# ownduino-tiny-cdc.net
KiCad netlist of a schematic drawn in EAGLE
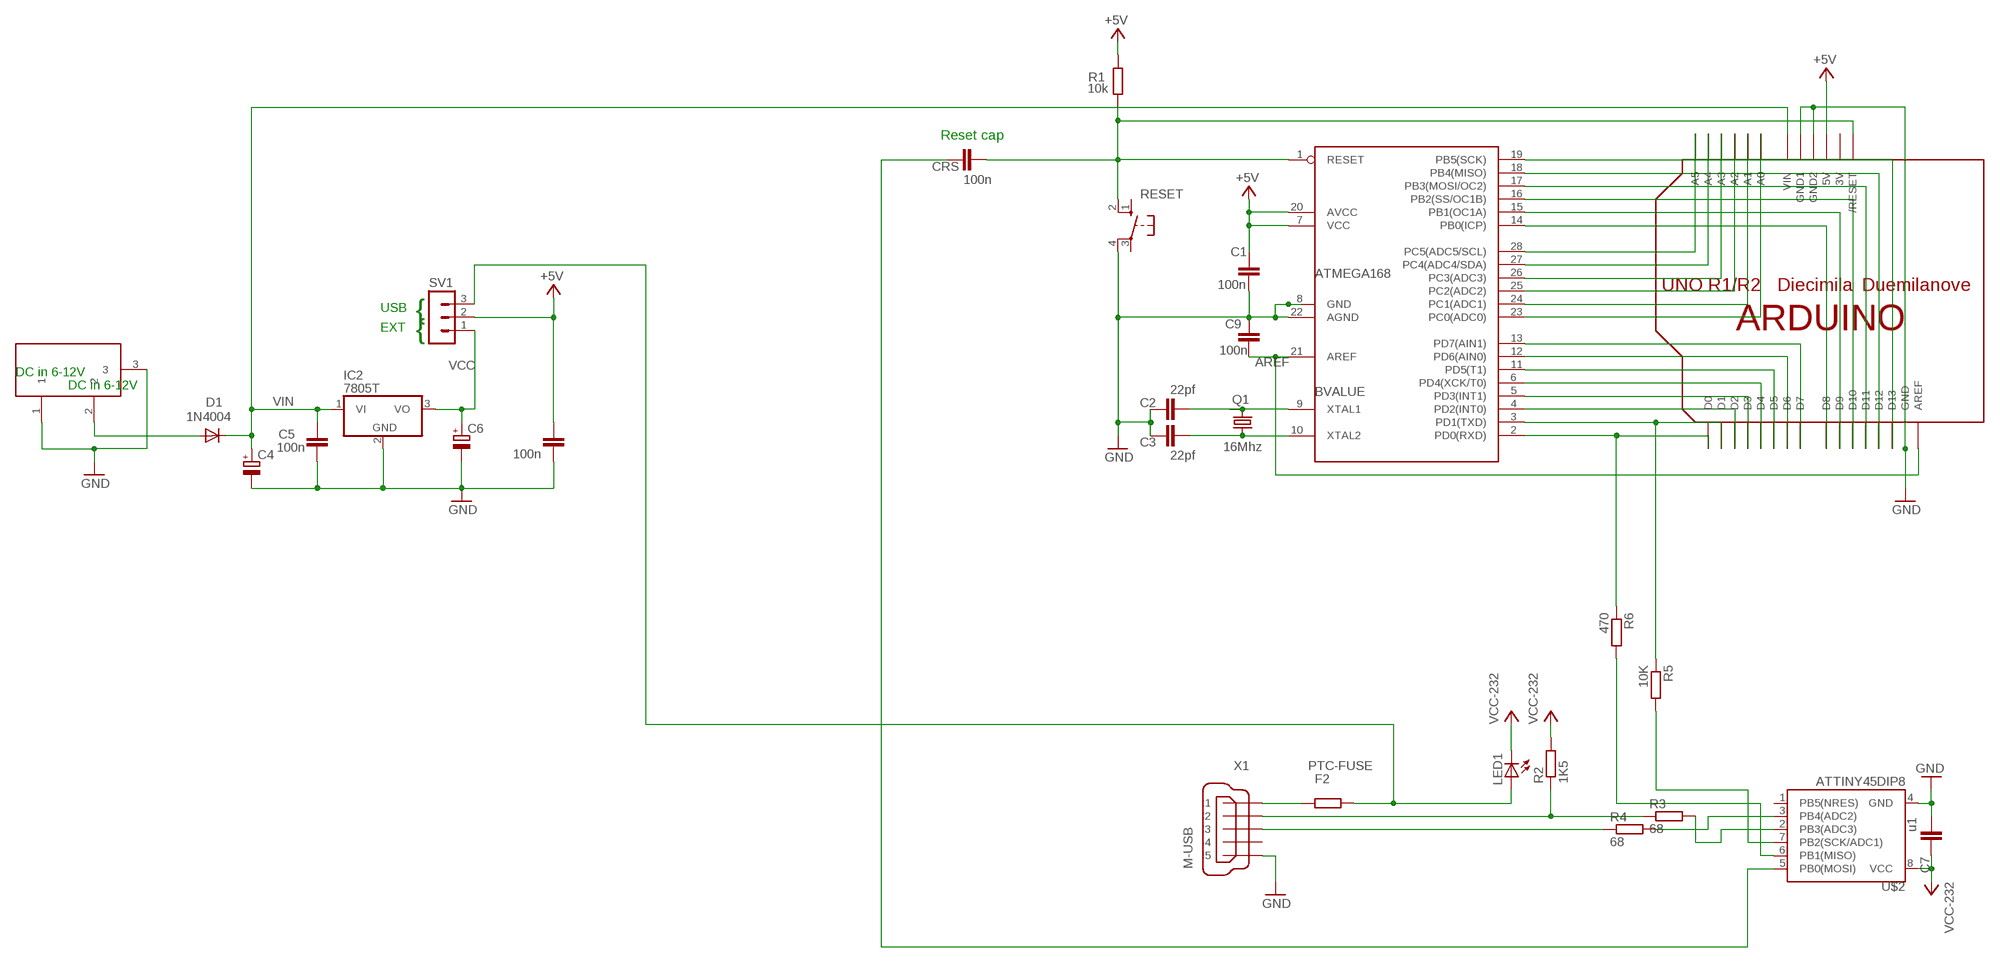
[diagram p0: schematic, sheet 1]

(export (version "E")
  (design (tool "Eeschema 10.0.6"))
  (components
    (comp (ref "BVALUE")
      (value "ATMEGA168")
      (footprint "eagle-import:DIL28-3")
      (libsource (lib "eagle-import") (part "MEGA8-P"))
    )
    (comp (ref "C1")
      (value "100n")
      (footprint "eagle-import:C025-024X044")
      (libsource (lib "eagle-import") (part "C-EU025-024X044"))
    )
    (comp (ref "C2")
      (value "22pf")
      (footprint "eagle-import:C025-024X044")
      (libsource (lib "eagle-import") (part "C-EU025-024X044"))
    )
    (comp (ref "C3")
      (value "22pf")
      (footprint "eagle-import:C025-024X044")
      (libsource (lib "eagle-import") (part "C-EU025-024X044"))
    )
    (comp (ref "C4")
      (value "CPOL-EUE2.5-6")
      (footprint "eagle-import:E2,5-6")
      (libsource (lib "eagle-import") (part "CPOL-EUE2.5-6"))
    )
    (comp (ref "C5")
      (value "100n")
      (footprint "eagle-import:C025-024X044")
      (libsource (lib "eagle-import") (part "C-EU025-024X044"))
    )
    (comp (ref "C6")
      (value "CPOL-EUE2.5-6")
      (footprint "eagle-import:E2,5-6")
      (libsource (lib "eagle-import") (part "CPOL-EUE2.5-6"))
    )
    (comp (ref "C7")
      (value "u1")
      (footprint "eagle-import:C025-024X044")
      (libsource (lib "eagle-import") (part "C-EU025-024X044"))
    )
    (comp (ref "C9")
      (value "100n")
      (footprint "eagle-import:C025-024X044")
      (libsource (lib "eagle-import") (part "C-EU025-024X044"))
    )
    (comp (ref "C10")
      (value "100n")
      (footprint "eagle-import:C025-024X044")
      (libsource (lib "eagle-import") (part "C-EU025-024X044"))
    )
    (comp (ref "CRS")
      (value "100n")
      (footprint "eagle-import:C025-024X044")
      (libsource (lib "eagle-import") (part "C-EU025-024X044"))
    )
    (comp (ref "D1")
      (value "1N4004")
      (footprint "eagle-import:DIODE-0.4")
      (libsource (lib "eagle-import") (part "DIODEPTH"))
    )
    (comp (ref "DC1")
      (value "9V in")
      (footprint "eagle-import:DC-21MM")
      (libsource (lib "eagle-import") (part "DC21MMX"))
    )
    (comp (ref "F2")
      (value "PTC-FUSE")
      (footprint "eagle-import:0204_5")
      (libsource (lib "eagle-import") (part "R-EU_0204/5"))
    )
    (comp (ref "IC2")
      (value "7805T")
      (footprint "eagle-import:TO220H")
      (libsource (lib "eagle-import") (part "78T05"))
    )
    (comp (ref "LED1")
      (value "LED3MM")
      (footprint "eagle-import:LED3MM")
      (libsource (lib "eagle-import") (part "LED3MM"))
    )
    (comp (ref "Q1")
      (value "16Mhz")
      (footprint "eagle-import:HC49U-V")
      (libsource (lib "eagle-import") (part "CRYSTALHC49U-V"))
    )
    (comp (ref "R1")
      (value "10k")
      (footprint "eagle-import:0204_7")
      (libsource (lib "eagle-import") (part "R-EU_0204/7"))
    )
    (comp (ref "R2")
      (value "1K5")
      (footprint "eagle-import:0204V")
      (libsource (lib "eagle-import") (part "R-EU_0204/2V"))
    )
    (comp (ref "R3")
      (value "68")
      (footprint "eagle-import:0204V")
      (libsource (lib "eagle-import") (part "R-EU_0204/2V"))
    )
    (comp (ref "R4")
      (value "68")
      (footprint "eagle-import:0204_5")
      (libsource (lib "eagle-import") (part "R-EU_0204/5"))
    )
    (comp (ref "R5")
      (value "10K")
      (footprint "eagle-import:0204_7")
      (libsource (lib "eagle-import") (part "R-EU_0204/7"))
    )
    (comp (ref "R6")
      (value "470")
      (footprint "eagle-import:0204_7")
      (libsource (lib "eagle-import") (part "R-EU_0204/7"))
    )
    (comp (ref "RESET")
      (value "10-XX")
      (footprint "eagle-import:B3F-10XX")
      (libsource (lib "eagle-import") (part "10-XX"))
    )
    (comp (ref "SV1")
      (value "MA03-1")
      (footprint "eagle-import:MA03-1")
      (libsource (lib "eagle-import") (part "MA03-1"))
    )
    (comp (ref "U$1")
      (value "ARDUINOUNO")
      (footprint "eagle-import:ARDUINO")
      (libsource (lib "eagle-import") (part "ARDUINOUNO"))
    )
    (comp (ref "U$2")
      (value "ATTINY45DIP8")
      (footprint "eagle-import:DIP08")
      (libsource (lib "eagle-import") (part "ATTINY45DIP8"))
    )
    (comp (ref "X1")
      (value "M-USB")
      (footprint "eagle-import:32005-601")
      (libsource (lib "eagle-import") (part "MINI-USB_SHIELD5P2-32005-601"))
    )
  )
  (nets
    (net (code "1") (name "+5V") (class "Default")
      (node (ref "BVALUE") (pin "20") (pinfunction "AVCC_20") (pintype "bidirectional"))
      (node (ref "BVALUE") (pin "7") (pinfunction "VCC_7") (pintype "bidirectional"))
      (node (ref "C1") (pin "1") (pinfunction "1_1") (pintype "passive"))
      (node (ref "C10") (pin "2") (pinfunction "2_2") (pintype "passive"))
      (node (ref "R1") (pin "2") (pinfunction "2_2") (pintype "passive"))
      (node (ref "SV1") (pin "2") (pinfunction "2_2") (pintype "passive"))
      (node (ref "U$1") (pin "5V") (pinfunction "5V_5V") (pintype "power_in"))
    )
    (net (code "2") (name "/3V") (class "Default")
      (node (ref "U$1") (pin "3V") (pinfunction "3V_3V") (pintype "power_in"))
    )
    (net (code "3") (name "/AREF") (class "Default")
      (node (ref "BVALUE") (pin "21") (pinfunction "AREF_21") (pintype "bidirectional"))
      (node (ref "C9") (pin "1") (pinfunction "1_1") (pintype "passive"))
      (node (ref "U$1") (pin "AREF") (pinfunction "AREF_AREF") (pintype "bidirectional"))
    )
    (net (code "4") (name "/VIN") (class "Default")
      (node (ref "C4") (pin "+") (pinfunction "+_+") (pintype "passive"))
      (node (ref "C5") (pin "2") (pinfunction "2_2") (pintype "passive"))
      (node (ref "D1") (pin "C") (pinfunction "C_C") (pintype "passive"))
      (node (ref "IC2") (pin "1") (pinfunction "VI_1") (pintype "input"))
      (node (ref "U$1") (pin "VIN") (pinfunction "VIN_VIN") (pintype "power_in"))
    )
    (net (code "5") (name "GND") (class "Default")
      (node (ref "BVALUE") (pin "22") (pinfunction "AGND_22") (pintype "bidirectional"))
      (node (ref "BVALUE") (pin "8") (pinfunction "GND_8") (pintype "bidirectional"))
      (node (ref "C1") (pin "2") (pinfunction "2_2") (pintype "passive"))
      (node (ref "C10") (pin "1") (pinfunction "1_1") (pintype "passive"))
      (node (ref "C2") (pin "1") (pinfunction "1_1") (pintype "passive"))
      (node (ref "C3") (pin "1") (pinfunction "1_1") (pintype "passive"))
      (node (ref "C4") (pin "-") (pinfunction "-_-") (pintype "passive"))
      (node (ref "C5") (pin "1") (pinfunction "1_1") (pintype "passive"))
      (node (ref "C6") (pin "-") (pinfunction "-_-") (pintype "passive"))
      (node (ref "C7") (pin "2") (pinfunction "2_2") (pintype "passive"))
      (node (ref "C9") (pin "2") (pinfunction "2_2") (pintype "passive"))
      (node (ref "DC1") (pin "1") (pinfunction "1_1") (pintype "power_in"))
      (node (ref "DC1") (pin "3") (pinfunction "3_3") (pintype "power_in"))
      (node (ref "IC2") (pin "2") (pinfunction "GND_2") (pintype "passive"))
      (node (ref "RESET") (pin "4") (pinfunction "P1_4") (pintype "passive"))
      (node (ref "U$1") (pin "GND") (pinfunction "GND_GND") (pintype "power_in"))
      (node (ref "U$1") (pin "GND1") (pinfunction "GND1_GND1") (pintype "power_in"))
      (node (ref "U$1") (pin "GND2") (pinfunction "GND2_GND2") (pintype "power_in"))
      (node (ref "U$2") (pin "4") (pinfunction "GND_4") (pintype "bidirectional"))
      (node (ref "X1") (pin "5") (pinfunction "5_5") (pintype "passive"))
    )
    (net (code "6") (name "Net-(BVALUE-PB0(ICP))") (class "Default")
      (node (ref "BVALUE") (pin "14") (pinfunction "PB0(ICP)_14") (pintype "bidirectional"))
      (node (ref "U$1") (pin "D8") (pinfunction "D8_D8") (pintype "bidirectional"))
    )
    (net (code "7") (name "Net-(BVALUE-PB1(OC1A))") (class "Default")
      (node (ref "BVALUE") (pin "15") (pinfunction "PB1(OC1A)_15") (pintype "bidirectional"))
      (node (ref "U$1") (pin "D9") (pinfunction "D9_D9") (pintype "bidirectional"))
    )
    (net (code "8") (name "Net-(BVALUE-PB2(SS{slash}OC1B))") (class "Default")
      (node (ref "BVALUE") (pin "16") (pinfunction "PB2(SS/OC1B)_16") (pintype "bidirectional"))
      (node (ref "U$1") (pin "D10") (pinfunction "D10_D10") (pintype "bidirectional"))
    )
    (net (code "9") (name "Net-(BVALUE-PB3(MOSI{slash}OC2))") (class "Default")
      (node (ref "BVALUE") (pin "17") (pinfunction "PB3(MOSI/OC2)_17") (pintype "bidirectional"))
      (node (ref "U$1") (pin "D11") (pinfunction "D11_D11") (pintype "bidirectional"))
    )
    (net (code "10") (name "Net-(BVALUE-PB4(MISO))") (class "Default")
      (node (ref "BVALUE") (pin "18") (pinfunction "PB4(MISO)_18") (pintype "bidirectional"))
      (node (ref "U$1") (pin "D12") (pinfunction "D12_D12") (pintype "bidirectional"))
    )
    (net (code "11") (name "Net-(BVALUE-PB5(SCK))") (class "Default")
      (node (ref "BVALUE") (pin "19") (pinfunction "PB5(SCK)_19") (pintype "bidirectional"))
      (node (ref "U$1") (pin "D13") (pinfunction "D13_D13") (pintype "bidirectional"))
    )
    (net (code "12") (name "Net-(BVALUE-PC0(ADC0))") (class "Default")
      (node (ref "BVALUE") (pin "23") (pinfunction "PC0(ADC0)_23") (pintype "bidirectional"))
      (node (ref "U$1") (pin "A0") (pinfunction "A0_A0") (pintype "bidirectional"))
    )
    (net (code "13") (name "Net-(BVALUE-PC1(ADC1))") (class "Default")
      (node (ref "BVALUE") (pin "24") (pinfunction "PC1(ADC1)_24") (pintype "bidirectional"))
      (node (ref "U$1") (pin "A1") (pinfunction "A1_A1") (pintype "bidirectional"))
    )
    (net (code "14") (name "Net-(BVALUE-PC2(ADC2))") (class "Default")
      (node (ref "BVALUE") (pin "25") (pinfunction "PC2(ADC2)_25") (pintype "bidirectional"))
      (node (ref "U$1") (pin "A2") (pinfunction "A2_A2") (pintype "bidirectional"))
    )
    (net (code "15") (name "Net-(BVALUE-PC3(ADC3))") (class "Default")
      (node (ref "BVALUE") (pin "26") (pinfunction "PC3(ADC3)_26") (pintype "bidirectional"))
      (node (ref "U$1") (pin "A3") (pinfunction "A3_A3") (pintype "bidirectional"))
    )
    (net (code "16") (name "Net-(BVALUE-PC4(ADC4{slash}SDA))") (class "Default")
      (node (ref "BVALUE") (pin "27") (pinfunction "PC4(ADC4/SDA)_27") (pintype "bidirectional"))
      (node (ref "U$1") (pin "A4") (pinfunction "A4_A4") (pintype "bidirectional"))
    )
    (net (code "17") (name "Net-(BVALUE-PC5(ADC5{slash}SCL))") (class "Default")
      (node (ref "BVALUE") (pin "28") (pinfunction "PC5(ADC5/SCL)_28") (pintype "bidirectional"))
      (node (ref "U$1") (pin "A5") (pinfunction "A5_A5") (pintype "bidirectional"))
    )
    (net (code "18") (name "Net-(BVALUE-PD0(RXD))") (class "Default")
      (node (ref "BVALUE") (pin "2") (pinfunction "PD0(RXD)_2") (pintype "bidirectional"))
      (node (ref "R6") (pin "1") (pinfunction "1_1") (pintype "passive"))
      (node (ref "U$1") (pin "D0") (pinfunction "D0_D0") (pintype "bidirectional"))
    )
    (net (code "19") (name "Net-(BVALUE-PD1(TXD))") (class "Default")
      (node (ref "BVALUE") (pin "3") (pinfunction "PD1(TXD)_3") (pintype "bidirectional"))
      (node (ref "R5") (pin "1") (pinfunction "1_1") (pintype "passive"))
      (node (ref "U$1") (pin "D1") (pinfunction "D1_D1") (pintype "bidirectional"))
    )
    (net (code "20") (name "Net-(BVALUE-PD2(INT0))") (class "Default")
      (node (ref "BVALUE") (pin "4") (pinfunction "PD2(INT0)_4") (pintype "bidirectional"))
      (node (ref "U$1") (pin "D2") (pinfunction "D2_D2") (pintype "bidirectional"))
    )
    (net (code "21") (name "Net-(BVALUE-PD3(INT1))") (class "Default")
      (node (ref "BVALUE") (pin "5") (pinfunction "PD3(INT1)_5") (pintype "bidirectional"))
      (node (ref "U$1") (pin "D3") (pinfunction "D3_D3") (pintype "bidirectional"))
    )
    (net (code "22") (name "Net-(BVALUE-PD4(XCK{slash}T0))") (class "Default")
      (node (ref "BVALUE") (pin "6") (pinfunction "PD4(XCK/T0)_6") (pintype "bidirectional"))
      (node (ref "U$1") (pin "D4") (pinfunction "D4_D4") (pintype "bidirectional"))
    )
    (net (code "23") (name "Net-(BVALUE-PD5(T1))") (class "Default")
      (node (ref "BVALUE") (pin "11") (pinfunction "PD5(T1)_11") (pintype "bidirectional"))
      (node (ref "U$1") (pin "D5") (pinfunction "D5_D5") (pintype "bidirectional"))
    )
    (net (code "24") (name "Net-(BVALUE-PD6(AIN0))") (class "Default")
      (node (ref "BVALUE") (pin "12") (pinfunction "PD6(AIN0)_12") (pintype "bidirectional"))
      (node (ref "U$1") (pin "D6") (pinfunction "D6_D6") (pintype "bidirectional"))
    )
    (net (code "25") (name "Net-(BVALUE-PD7(AIN1))") (class "Default")
      (node (ref "BVALUE") (pin "13") (pinfunction "PD7(AIN1)_13") (pintype "bidirectional"))
      (node (ref "U$1") (pin "D7") (pinfunction "D7_D7") (pintype "bidirectional"))
    )
    (net (code "26") (name "Net-(BVALUE-RESET)") (class "Default")
      (node (ref "BVALUE") (pin "1") (pinfunction "RESET_1") (pintype "bidirectional"))
      (node (ref "CRS") (pin "2") (pinfunction "2_2") (pintype "passive"))
      (node (ref "R1") (pin "1") (pinfunction "1_1") (pintype "passive"))
      (node (ref "RESET") (pin "2") (pinfunction "S1_2") (pintype "passive"))
      (node (ref "U$1") (pin "RESET") (pinfunction "/RESET_RESET") (pintype "bidirectional"))
    )
    (net (code "27") (name "Net-(BVALUE-XTAL1)") (class "Default")
      (node (ref "BVALUE") (pin "9") (pinfunction "XTAL1_9") (pintype "bidirectional"))
      (node (ref "C2") (pin "2") (pinfunction "2_2") (pintype "passive"))
      (node (ref "Q1") (pin "2") (pinfunction "2_2") (pintype "passive"))
    )
    (net (code "28") (name "Net-(BVALUE-XTAL2)") (class "Default")
      (node (ref "BVALUE") (pin "10") (pinfunction "XTAL2_10") (pintype "bidirectional"))
      (node (ref "C3") (pin "2") (pinfunction "2_2") (pintype "passive"))
      (node (ref "Q1") (pin "1") (pinfunction "1_1") (pintype "passive"))
    )
    (net (code "29") (name "Net-(D1-PadA)") (class "Default")
      (node (ref "D1") (pin "A") (pinfunction "A_A") (pintype "passive"))
      (node (ref "DC1") (pin "2") (pinfunction "2_2") (pintype "power_in"))
    )
    (net (code "30") (name "Net-(F2-Pad1)") (class "Default")
      (node (ref "F2") (pin "1") (pinfunction "1_1") (pintype "passive"))
      (node (ref "LED1") (pin "A") (pinfunction "A_A") (pintype "passive"))
      (node (ref "SV1") (pin "3") (pinfunction "3_3") (pintype "passive"))
    )
    (net (code "31") (name "Net-(F2-Pad2)") (class "Default")
      (node (ref "F2") (pin "2") (pinfunction "2_2") (pintype "passive"))
      (node (ref "X1") (pin "1") (pinfunction "1_1") (pintype "passive"))
    )
    (net (code "32") (name "Net-(R2-Pad1)") (class "Default")
      (node (ref "R2") (pin "1") (pinfunction "1_1") (pintype "passive"))
      (node (ref "R3") (pin "1") (pinfunction "1_1") (pintype "passive"))
      (node (ref "X1") (pin "2") (pinfunction "2_2") (pintype "passive"))
    )
    (net (code "33") (name "Net-(R4-Pad1)") (class "Default")
      (node (ref "R4") (pin "1") (pinfunction "1_1") (pintype "passive"))
      (node (ref "X1") (pin "3") (pinfunction "3_3") (pintype "passive"))
    )
    (net (code "34") (name "Net-(U$2-PB0(MOSI))") (class "Default")
      (node (ref "CRS") (pin "1") (pinfunction "1_1") (pintype "passive"))
      (node (ref "U$2") (pin "5") (pinfunction "PB0(MOSI)_5") (pintype "bidirectional"))
    )
    (net (code "35") (name "Net-(U$2-PB1(MISO))") (class "Default")
      (node (ref "R6") (pin "2") (pinfunction "2_2") (pintype "passive"))
      (node (ref "U$2") (pin "6") (pinfunction "PB1(MISO)_6") (pintype "bidirectional"))
    )
    (net (code "36") (name "Net-(U$2-PB2(SCK{slash}ADC1))") (class "Default")
      (node (ref "R5") (pin "2") (pinfunction "2_2") (pintype "passive"))
      (node (ref "U$2") (pin "7") (pinfunction "PB2(SCK/ADC1)_7") (pintype "bidirectional"))
    )
    (net (code "37") (name "Net-(U$2-PB3(ADC3))") (class "Default")
      (node (ref "R3") (pin "2") (pinfunction "2_2") (pintype "passive"))
      (node (ref "U$2") (pin "2") (pinfunction "PB3(ADC3)_2") (pintype "bidirectional"))
    )
    (net (code "38") (name "Net-(U$2-PB4(ADC2))") (class "Default")
      (node (ref "R4") (pin "2") (pinfunction "2_2") (pintype "passive"))
      (node (ref "U$2") (pin "3") (pinfunction "PB4(ADC2)_3") (pintype "bidirectional"))
    )
    (net (code "39") (name "VCC-232") (class "Default")
      (node (ref "C6") (pin "+") (pinfunction "+_+") (pintype "passive"))
      (node (ref "C7") (pin "1") (pinfunction "1_1") (pintype "passive"))
      (node (ref "IC2") (pin "3") (pinfunction "VO_3") (pintype "passive"))
      (node (ref "LED1") (pin "K") (pinfunction "C_K") (pintype "passive"))
      (node (ref "R2") (pin "2") (pinfunction "2_2") (pintype "passive"))
      (node (ref "SV1") (pin "1") (pinfunction "1_1") (pintype "passive"))
      (node (ref "U$2") (pin "8") (pinfunction "VCC_8") (pintype "bidirectional"))
    )
    (net (code "40") (name "unconnected-(RESET-P-Pad3)") (class "Default")
      (node (ref "RESET") (pin "3") (pinfunction "P_3") (pintype "passive"))
    )
    (net (code "41") (name "unconnected-(RESET-S-Pad1)") (class "Default")
      (node (ref "RESET") (pin "1") (pinfunction "S_1") (pintype "passive"))
    )
    (net (code "42") (name "unconnected-(U$2-PB5(NRES)-Pad1)") (class "Default")
      (node (ref "U$2") (pin "1") (pinfunction "PB5(NRES)_1") (pintype "bidirectional"))
    )
    (net (code "43") (name "unconnected-(X1-Pad4)") (class "Default")
      (node (ref "X1") (pin "4") (pinfunction "4_4") (pintype "passive"))
    )
  )
)
